# 7W_Audio_Amplifier.net
KiCad netlist of a schematic drawn in EAGLE
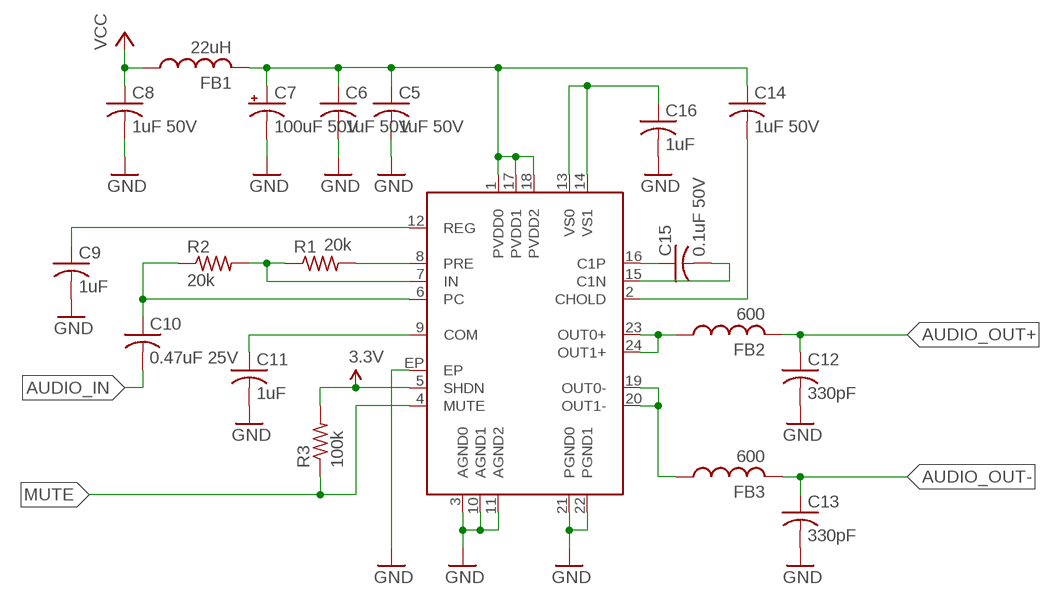
[diagram p0: schematic, sheet 1]

(export (version "E")
  (design (tool "Eeschema 10.0.6"))
  (components
    (comp (ref "C5")
      (value "1uF 50V")
      (footprint "eagle-import:0805_CAP")
      (libsource (lib "eagle-import") (part "CAP0805"))
    )
    (comp (ref "C6")
      (value "1uF 50V")
      (footprint "eagle-import:0805_CAP")
      (libsource (lib "eagle-import") (part "CAP0805"))
    )
    (comp (ref "C7")
      (value "100uF 50V")
      (footprint "eagle-import:F_CAP")
      (libsource (lib "eagle-import") (part "CAP_POLF"))
    )
    (comp (ref "C8")
      (value "1uF 50V")
      (footprint "eagle-import:0805_CAP")
      (libsource (lib "eagle-import") (part "CAP0805"))
    )
    (comp (ref "C9")
      (value "1uF")
      (footprint "eagle-import:0603_CAP")
      (libsource (lib "eagle-import") (part "CAP0603"))
    )
    (comp (ref "C10")
      (value "0.47uF 25V")
      (footprint "eagle-import:0603_CAP")
      (libsource (lib "eagle-import") (part "CAP0603"))
    )
    (comp (ref "C11")
      (value "1uF")
      (footprint "eagle-import:0603_CAP")
      (libsource (lib "eagle-import") (part "CAP0603"))
    )
    (comp (ref "C12")
      (value "330pF")
      (footprint "eagle-import:0603_CAP")
      (libsource (lib "eagle-import") (part "CAP0603"))
    )
    (comp (ref "C13")
      (value "330pF")
      (footprint "eagle-import:0603_CAP")
      (libsource (lib "eagle-import") (part "CAP0603"))
    )
    (comp (ref "C14")
      (value "1uF 50V")
      (footprint "eagle-import:0805_CAP")
      (libsource (lib "eagle-import") (part "CAP0805"))
    )
    (comp (ref "C15")
      (value "0.1uF 50V")
      (footprint "eagle-import:0603_CAP")
      (libsource (lib "eagle-import") (part "CAP0603"))
    )
    (comp (ref "C16")
      (value "1uF")
      (footprint "eagle-import:0603_CAP")
      (libsource (lib "eagle-import") (part "CAP0603"))
    )
    (comp (ref "FB1")
      (value "22uH")
      (footprint "eagle-import:0805_FB")
      (libsource (lib "eagle-import") (part "FB0805"))
    )
    (comp (ref "FB2")
      (value "600")
      (footprint "eagle-import:0805_FB")
      (libsource (lib "eagle-import") (part "FB0805"))
    )
    (comp (ref "FB3")
      (value "600")
      (footprint "eagle-import:0805_FB")
      (libsource (lib "eagle-import") (part "FB0805"))
    )
    (comp (ref "MAX1")
      (value "MAX9737")
      (footprint "eagle-import:TQFN24")
      (fields (field (name "MANF") "Maxim"))
      (libsource (lib "eagle-import") (part "MAX9737"))
    )
    (comp (ref "R1")
      (value "20k")
      (footprint "eagle-import:0603_RESISTOR")
      (libsource (lib "eagle-import") (part "RESISTOR0603"))
    )
    (comp (ref "R2")
      (value "20k")
      (footprint "eagle-import:0603_RESISTOR")
      (libsource (lib "eagle-import") (part "RESISTOR0603"))
    )
    (comp (ref "R3")
      (value "100k")
      (footprint "eagle-import:0603_RESISTOR")
      (libsource (lib "eagle-import") (part "RESISTOR0603"))
    )
  )
  (nets
    (net (code "1") (name "3.3V") (class "Default")
      (node (ref "MAX1") (pin "5") (pinfunction "SHDN_5") (pintype "input"))
      (node (ref "R3") (pin "2") (pinfunction "2_2") (pintype "passive"))
    )
    (net (code "2") (name "AUDIO_IN") (class "Default")
      (node (ref "C10") (pin "2") (pinfunction "2_2") (pintype "passive"))
    )
    (net (code "3") (name "AUDIO_OUT+") (class "Default")
      (node (ref "C12") (pin "1") (pinfunction "1_1") (pintype "passive"))
      (node (ref "FB2") (pin "2") (pinfunction "2_2") (pintype "passive"))
    )
    (net (code "4") (name "AUDIO_OUT-") (class "Default")
      (node (ref "C13") (pin "1") (pinfunction "1_1") (pintype "passive"))
      (node (ref "FB3") (pin "2") (pinfunction "2_2") (pintype "passive"))
    )
    (net (code "5") (name "GND") (class "Default")
      (node (ref "C11") (pin "2") (pinfunction "2_2") (pintype "passive"))
      (node (ref "C12") (pin "2") (pinfunction "2_2") (pintype "passive"))
      (node (ref "C13") (pin "2") (pinfunction "2_2") (pintype "passive"))
      (node (ref "C16") (pin "2") (pinfunction "2_2") (pintype "passive"))
      (node (ref "C5") (pin "2") (pinfunction "2_2") (pintype "passive"))
      (node (ref "C6") (pin "2") (pinfunction "2_2") (pintype "passive"))
      (node (ref "C7") (pin "-") (pinfunction "-_-") (pintype "passive"))
      (node (ref "C8") (pin "2") (pinfunction "2_2") (pintype "passive"))
      (node (ref "C9") (pin "2") (pinfunction "2_2") (pintype "passive"))
      (node (ref "MAX1") (pin "10") (pinfunction "AGND1_10") (pintype "power_in"))
      (node (ref "MAX1") (pin "11") (pinfunction "AGND2_11") (pintype "power_in"))
      (node (ref "MAX1") (pin "21") (pinfunction "PGND0_21") (pintype "power_in"))
      (node (ref "MAX1") (pin "22") (pinfunction "PGND1_22") (pintype "power_in"))
      (node (ref "MAX1") (pin "3") (pinfunction "AGND0_3") (pintype "power_in"))
      (node (ref "MAX1") (pin "EP") (pinfunction "EP_EP") (pintype "passive"))
    )
    (net (code "6") (name "MUTE") (class "Default")
      (node (ref "MAX1") (pin "4") (pinfunction "MUTE_4") (pintype "input"))
      (node (ref "R3") (pin "1") (pinfunction "1_1") (pintype "passive"))
    )
    (net (code "7") (name "Net-(MAX1-C1N)") (class "Default")
      (node (ref "C15") (pin "2") (pinfunction "2_2") (pintype "passive"))
      (node (ref "MAX1") (pin "15") (pinfunction "C1N_15") (pintype "output"))
    )
    (net (code "8") (name "Net-(MAX1-C1P)") (class "Default")
      (node (ref "C15") (pin "1") (pinfunction "1_1") (pintype "passive"))
      (node (ref "MAX1") (pin "16") (pinfunction "C1P_16") (pintype "output"))
    )
    (net (code "9") (name "Net-(MAX1-CHOLD)") (class "Default")
      (node (ref "C14") (pin "2") (pinfunction "2_2") (pintype "passive"))
      (node (ref "MAX1") (pin "2") (pinfunction "CHOLD_2") (pintype "output"))
    )
    (net (code "10") (name "Net-(MAX1-COM)") (class "Default")
      (node (ref "C11") (pin "1") (pinfunction "1_1") (pintype "passive"))
      (node (ref "MAX1") (pin "9") (pinfunction "COM_9") (pintype "input"))
    )
    (net (code "11") (name "Net-(MAX1-IN)") (class "Default")
      (node (ref "MAX1") (pin "7") (pinfunction "IN_7") (pintype "input"))
      (node (ref "R1") (pin "1") (pinfunction "1_1") (pintype "passive"))
      (node (ref "R2") (pin "2") (pinfunction "2_2") (pintype "passive"))
    )
    (net (code "12") (name "Net-(MAX1-OUT0+)") (class "Default")
      (node (ref "FB2") (pin "1") (pinfunction "1_1") (pintype "passive"))
      (node (ref "MAX1") (pin "23") (pinfunction "OUT0+_23") (pintype "output"))
      (node (ref "MAX1") (pin "24") (pinfunction "OUT1+_24") (pintype "output"))
    )
    (net (code "13") (name "Net-(MAX1-OUT0-)") (class "Default")
      (node (ref "FB3") (pin "1") (pinfunction "1_1") (pintype "passive"))
      (node (ref "MAX1") (pin "19") (pinfunction "OUT0-_19") (pintype "output"))
      (node (ref "MAX1") (pin "20") (pinfunction "OUT1-_20") (pintype "output"))
    )
    (net (code "14") (name "Net-(MAX1-PC)") (class "Default")
      (node (ref "C10") (pin "1") (pinfunction "1_1") (pintype "passive"))
      (node (ref "MAX1") (pin "6") (pinfunction "PC_6") (pintype "input"))
      (node (ref "R2") (pin "1") (pinfunction "1_1") (pintype "passive"))
    )
    (net (code "15") (name "Net-(MAX1-PRE)") (class "Default")
      (node (ref "MAX1") (pin "8") (pinfunction "PRE_8") (pintype "output"))
      (node (ref "R1") (pin "2") (pinfunction "2_2") (pintype "passive"))
    )
    (net (code "16") (name "Net-(MAX1-PVDD0)") (class "Default")
      (node (ref "C14") (pin "1") (pinfunction "1_1") (pintype "passive"))
      (node (ref "C5") (pin "1") (pinfunction "1_1") (pintype "passive"))
      (node (ref "C6") (pin "1") (pinfunction "1_1") (pintype "passive"))
      (node (ref "C7") (pin "+") (pinfunction "+_+") (pintype "passive"))
      (node (ref "FB1") (pin "2") (pinfunction "2_2") (pintype "passive"))
      (node (ref "MAX1") (pin "1") (pinfunction "PVDD0_1") (pintype "power_in"))
      (node (ref "MAX1") (pin "17") (pinfunction "PVDD1_17") (pintype "power_in"))
      (node (ref "MAX1") (pin "18") (pinfunction "PVDD2_18") (pintype "power_in"))
    )
    (net (code "17") (name "Net-(MAX1-REG)") (class "Default")
      (node (ref "C9") (pin "1") (pinfunction "1_1") (pintype "passive"))
      (node (ref "MAX1") (pin "12") (pinfunction "REG_12") (pintype "output"))
    )
    (net (code "18") (name "Net-(MAX1-VS0)") (class "Default")
      (node (ref "C16") (pin "1") (pinfunction "1_1") (pintype "passive"))
      (node (ref "MAX1") (pin "13") (pinfunction "VS0_13") (pintype "output"))
      (node (ref "MAX1") (pin "14") (pinfunction "VS1_14") (pintype "output"))
    )
    (net (code "19") (name "VCC") (class "Default")
      (node (ref "C8") (pin "1") (pinfunction "1_1") (pintype "passive"))
      (node (ref "FB1") (pin "1") (pinfunction "1_1") (pintype "passive"))
    )
  )
)
